# BaseNode.net
KiCad netlist of a schematic drawn in Altium Designer
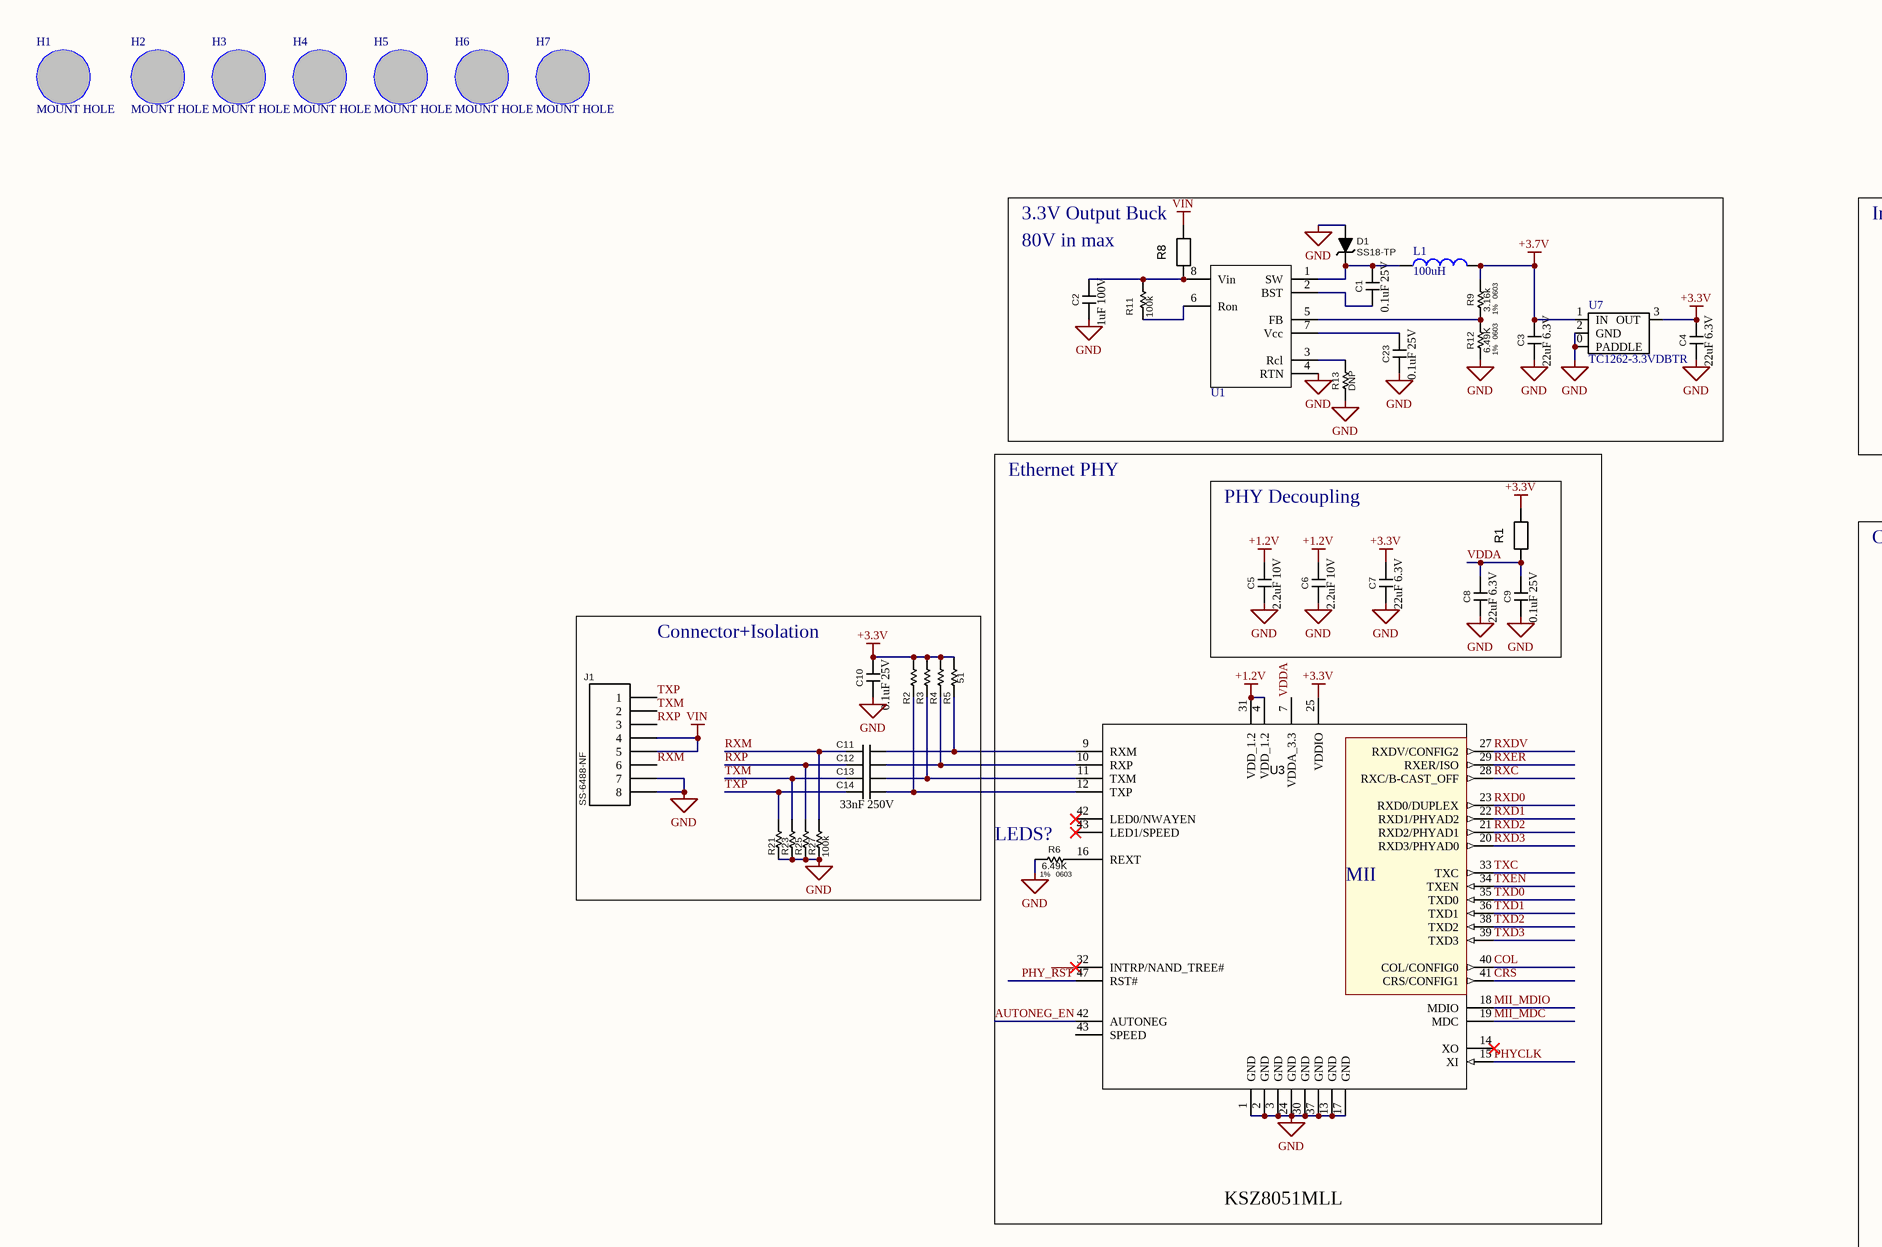
[diagram p0: BaseNode.SchDoc, top left]
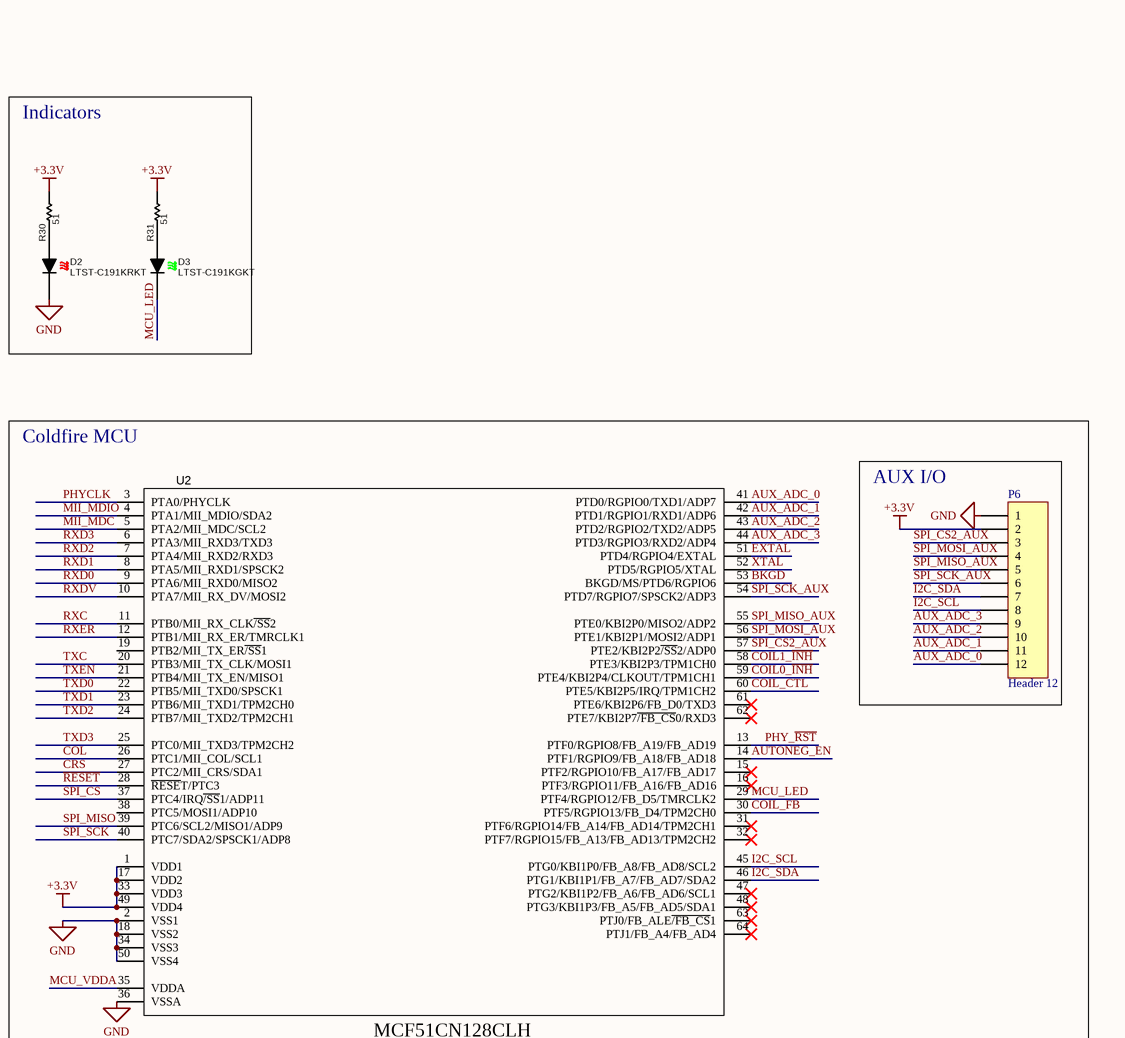
[diagram p1: BaseNode.SchDoc, top right]
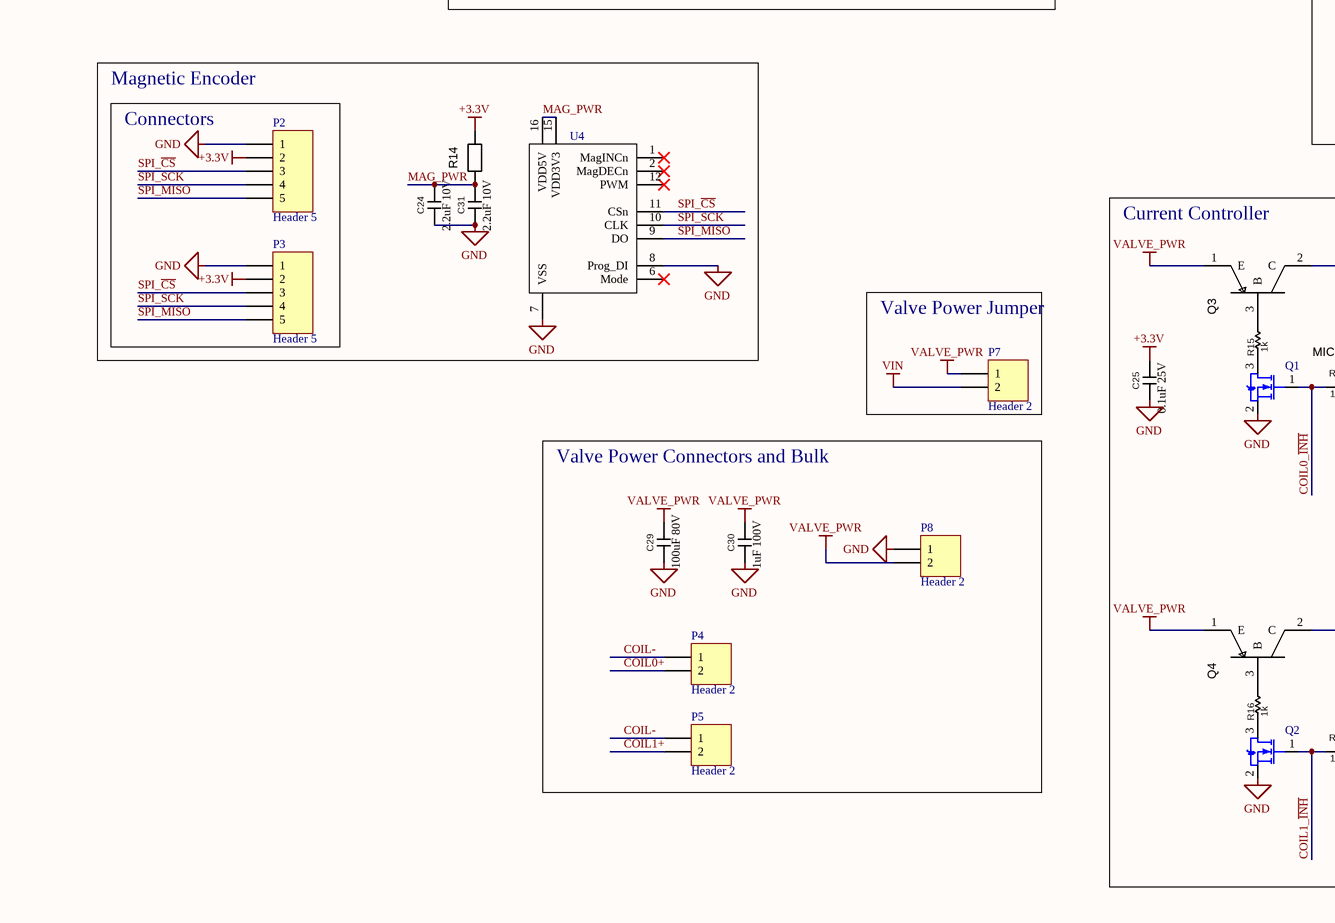
[diagram p2: BaseNode.SchDoc, bottom left]
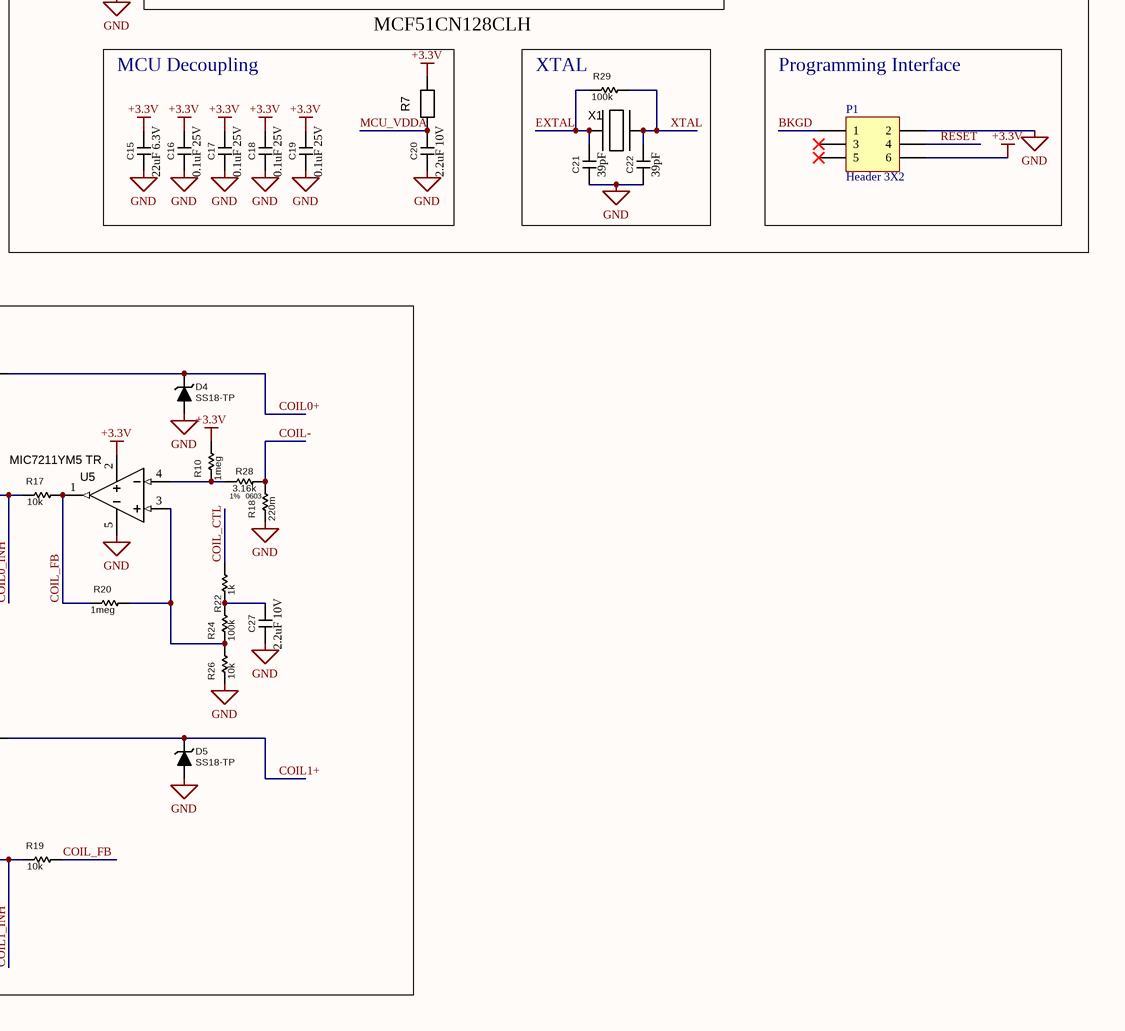
[diagram p3: BaseNode.SchDoc, bottom right]

(export (version "E")
  (design (tool "Eeschema 10.0.6"))
  (components
    (comp (ref "C1")
      (value "0.1uF 25V")
      (footprint "whong:0603")
      (description "Capacitor")
      (fields (field (name "MANUFACTURER") "Murata Electronics North America"))
      (libsource (lib "whong") (part "Capacitor"))
    )
    (comp (ref "C2")
      (value "1uF 100V")
      (footprint "whong:0805")
      (description "Capacitor")
      (fields (field (name "MANUFACTURER") "TDK Corporation"))
      (libsource (lib "whong") (part "Capacitor"))
    )
    (comp (ref "C3")
      (value "22uF 6.3V")
      (footprint "whong:1206")
      (description "Capacitor")
      (fields (field (name "MANUFACTURER") "Taiyo Yuden"))
      (libsource (lib "whong") (part "Capacitor"))
    )
    (comp (ref "C4")
      (value "22uF 6.3V")
      (footprint "whong:1206")
      (description "Capacitor")
      (fields (field (name "MANUFACTURER") "Taiyo Yuden"))
      (libsource (lib "whong") (part "Capacitor"))
    )
    (comp (ref "C5")
      (value "2.2uF 10V")
      (footprint "whong:0603")
      (description "Capacitor")
      (fields (field (name "MANUFACTURER") "Taiyo Yuden"))
      (libsource (lib "whong") (part "Capacitor"))
    )
    (comp (ref "C6")
      (value "2.2uF 10V")
      (footprint "whong:0603")
      (description "Capacitor")
      (fields (field (name "MANUFACTURER") "Taiyo Yuden"))
      (libsource (lib "whong") (part "Capacitor"))
    )
    (comp (ref "C7")
      (value "22uF 6.3V")
      (footprint "whong:1206")
      (description "Capacitor")
      (fields (field (name "MANUFACTURER") "Taiyo Yuden"))
      (libsource (lib "whong") (part "Capacitor"))
    )
    (comp (ref "C8")
      (value "22uF 6.3V")
      (footprint "whong:1206")
      (description "Capacitor")
      (fields (field (name "MANUFACTURER") "Taiyo Yuden"))
      (libsource (lib "whong") (part "Capacitor"))
    )
    (comp (ref "C9")
      (value "0.1uF 25V")
      (footprint "whong:0603")
      (description "Capacitor")
      (fields (field (name "MANUFACTURER") "Murata Electronics North America"))
      (libsource (lib "whong") (part "Capacitor"))
    )
    (comp (ref "C10")
      (value "0.1uF 25V")
      (footprint "whong:0603")
      (description "Capacitor")
      (fields (field (name "MANUFACTURER") "Murata Electronics North America"))
      (libsource (lib "whong") (part "Capacitor"))
    )
    (comp (ref "C11")
      (value "33nF 250V")
      (footprint "whong:0805")
      (description "Capacitor")
      (fields (field (name "MANUFACTURER") "TDK Corporation"))
      (libsource (lib "whong") (part "Capacitor"))
    )
    (comp (ref "C12")
      (value "33nF 250V")
      (footprint "whong:0805")
      (description "Capacitor")
      (fields (field (name "MANUFACTURER") "TDK Corporation"))
      (libsource (lib "whong") (part "Capacitor"))
    )
    (comp (ref "C13")
      (value "33nF 250V")
      (footprint "whong:0805")
      (description "Capacitor")
      (fields (field (name "MANUFACTURER") "TDK Corporation"))
      (libsource (lib "whong") (part "Capacitor"))
    )
    (comp (ref "C14")
      (value "33nF 250V")
      (footprint "whong:0805")
      (description "Capacitor")
      (fields (field (name "MANUFACTURER") "TDK Corporation"))
      (libsource (lib "whong") (part "Capacitor"))
    )
    (comp (ref "C15")
      (value "22uF 6.3V")
      (footprint "whong:1206")
      (description "Capacitor")
      (fields (field (name "MANUFACTURER") "Taiyo Yuden"))
      (libsource (lib "whong") (part "Capacitor"))
    )
    (comp (ref "C16")
      (value "0.1uF 25V")
      (footprint "whong:0603")
      (description "Capacitor")
      (fields (field (name "MANUFACTURER") "Murata Electronics North America"))
      (libsource (lib "whong") (part "Capacitor"))
    )
    (comp (ref "C17")
      (value "0.1uF 25V")
      (footprint "whong:0603")
      (description "Capacitor")
      (fields (field (name "MANUFACTURER") "Murata Electronics North America"))
      (libsource (lib "whong") (part "Capacitor"))
    )
    (comp (ref "C18")
      (value "0.1uF 25V")
      (footprint "whong:0603")
      (description "Capacitor")
      (fields (field (name "MANUFACTURER") "Murata Electronics North America"))
      (libsource (lib "whong") (part "Capacitor"))
    )
    (comp (ref "C19")
      (value "0.1uF 25V")
      (footprint "whong:0603")
      (description "Capacitor")
      (fields (field (name "MANUFACTURER") "Murata Electronics North America"))
      (libsource (lib "whong") (part "Capacitor"))
    )
    (comp (ref "C20")
      (value "2.2uF 10V")
      (footprint "whong:0603")
      (description "Capacitor")
      (fields (field (name "MANUFACTURER") "Taiyo Yuden"))
      (libsource (lib "whong") (part "Capacitor"))
    )
    (comp (ref "C21")
      (value "39pF")
      (footprint "whong:0603")
      (description "Capacitor")
      (fields (field (name "MANUFACTURER") "TDK Corporation"))
      (libsource (lib "whong") (part "Capacitor"))
    )
    (comp (ref "C22")
      (value "39pF")
      (footprint "whong:0603")
      (description "Capacitor")
      (fields (field (name "MANUFACTURER") "TDK Corporation"))
      (libsource (lib "whong") (part "Capacitor"))
    )
    (comp (ref "C23")
      (value "0.1uF 25V")
      (footprint "whong:0603")
      (description "Capacitor")
      (fields (field (name "MANUFACTURER") "Murata Electronics North America"))
      (libsource (lib "whong") (part "Capacitor"))
    )
    (comp (ref "C24")
      (value "2.2uF 10V")
      (footprint "whong:0603")
      (description "Capacitor")
      (fields (field (name "MANUFACTURER") "Taiyo Yuden"))
      (libsource (lib "whong") (part "Capacitor"))
    )
    (comp (ref "C25")
      (value "0.1uF 25V")
      (footprint "whong:0603")
      (description "Capacitor")
      (fields (field (name "MANUFACTURER") "Murata Electronics North America"))
      (libsource (lib "whong") (part "Capacitor"))
    )
    (comp (ref "C27")
      (value "2.2uF 10V")
      (footprint "whong:0603")
      (description "Capacitor")
      (fields (field (name "MANUFACTURER") "Taiyo Yuden"))
      (libsource (lib "whong") (part "Capacitor"))
    )
    (comp (ref "C29")
      (value "100uF 80V")
      (footprint "whong:Capacitor 12mm DIA POLAR")
      (description "Capacitor")
      (fields (field (name "MANUFACTURER") "Panasonic Electronic Components"))
      (libsource (lib "whong") (part "Capacitor"))
    )
    (comp (ref "C30")
      (value "1uF 100V")
      (footprint "whong:0805")
      (description "Capacitor")
      (fields (field (name "MANUFACTURER") "TDK Corporation"))
      (libsource (lib "whong") (part "Capacitor"))
    )
    (comp (ref "C31")
      (value "2.2uF 10V")
      (footprint "whong:0603")
      (description "Capacitor")
      (fields (field (name "MANUFACTURER") "Taiyo Yuden"))
      (libsource (lib "whong") (part "Capacitor"))
    )
    (comp (ref "D1")
      (value "CDBA140-G")
      (footprint "SMA-DIODE")
      (description "DIODE SCHOTTKY 40V 1A SMA")
      (fields (field (name "MANUFACTURER") "Micro Commercial Co") (field (name "MANUFACTURERPN") "SS18-TP"))
      (libsource (lib "whong") (part "CDBA140-G"))
    )
    (comp (ref "D2")
      (value "WP113IDT")
      (footprint "whong:0603 - LED")
      (description "LED RECT 2X5MM 625NM RED DIFF")
      (fields (field (name "MANUFACTURER") "Lite-On Inc") (field (name "MANUFACTURERPN") "LTST-C191KRKT"))
      (libsource (lib "whong") (part "WP113IDT"))
    )
    (comp (ref "D3")
      (value "WP113GDT")
      (footprint "whong:0603 - LED")
      (description "LED RECT 2X5MM 568NM GRN DIFF")
      (fields (field (name "MANUFACTURER") "Lite-On Inc") (field (name "MANUFACTURERPN") "LTST-C191KGKT"))
      (libsource (lib "whong") (part "WP113GDT"))
    )
    (comp (ref "D4")
      (value "CDBA140-G")
      (footprint "SMA-DIODE")
      (description "DIODE SCHOTTKY 40V 1A SMA")
      (fields (field (name "MANUFACTURER") "Micro Commercial Co") (field (name "MANUFACTURERPN") "SS18-TP"))
      (libsource (lib "whong") (part "CDBA140-G"))
    )
    (comp (ref "D5")
      (value "CDBA140-G")
      (footprint "SMA-DIODE")
      (description "DIODE SCHOTTKY 40V 1A SMA")
      (fields (field (name "MANUFACTURER") "Micro Commercial Co") (field (name "MANUFACTURERPN") "SS18-TP"))
      (libsource (lib "whong") (part "CDBA140-G"))
    )
    (comp (ref "H1")
      (value "MOUNT HOLE")
      (footprint "MOUNT_HOLE")
      (libsource (lib "whong") (part "MOUNT HOLE"))
    )
    (comp (ref "H2")
      (value "MOUNT HOLE")
      (footprint "MOUNT_HOLE")
      (libsource (lib "whong") (part "MOUNT HOLE"))
    )
    (comp (ref "H3")
      (value "MOUNT HOLE")
      (footprint "MOUNT_HOLE")
      (libsource (lib "whong") (part "MOUNT HOLE"))
    )
    (comp (ref "H4")
      (value "MOUNT HOLE")
      (footprint "MOUNT_HOLE")
      (libsource (lib "whong") (part "MOUNT HOLE"))
    )
    (comp (ref "H5")
      (value "MOUNT HOLE")
      (footprint "MOUNT_HOLE")
      (libsource (lib "whong") (part "MOUNT HOLE"))
    )
    (comp (ref "H6")
      (value "MOUNT HOLE")
      (footprint "MOUNT_HOLE")
      (libsource (lib "whong") (part "MOUNT HOLE"))
    )
    (comp (ref "H7")
      (value "MOUNT HOLE")
      (footprint "MOUNT_HOLE")
      (libsource (lib "whong") (part "MOUNT HOLE"))
    )
    (comp (ref "J1")
      (value "SS-6488-NF")
      (footprint "whong:SS-6488-NF")
      (description "CONN 8-8 MOD JACK")
      (fields (field (name "MANUFACTURER") "Stewart Connector"))
      (libsource (lib "whong") (part "SS-6488-NF"))
    )
    (comp (ref "L1")
      (value "100uH")
      (footprint "whong:NR6028 Inductor")
      (description "Inductor")
      (fields (field (name "MANUFACTURER") "Taiyo Yuden"))
      (libsource (lib "Miscellaneous Devices") (part "Inductor"))
    )
    (comp (ref "P1")
      (value "Header 3X2")
      (footprint "HDR2X3")
      (description "Header, 3-Pin, Dual row")
      (fields (field (name "PUBLISHER") "Altium Limited"))
      (libsource (lib "Miscellaneous Connectors") (part "Header 3X2"))
    )
    (comp (ref "P2")
      (value "Header 5")
      (footprint "HDR1X5")
      (description "Header, 5-Pin")
      (fields (field (name "PUBLISHER") "Altium Limited"))
      (libsource (lib "Miscellaneous Connectors") (part "Header 5"))
    )
    (comp (ref "P3")
      (value "Header 5")
      (footprint "HDR1X5")
      (description "Header, 5-Pin")
      (fields (field (name "PUBLISHER") "Altium Limited"))
      (libsource (lib "Miscellaneous Connectors") (part "Header 5"))
    )
    (comp (ref "P4")
      (value "Header 2")
      (footprint "HDR1X2")
      (description "Header, 2-Pin")
      (fields (field (name "PUBLISHER") "Altium Limited"))
      (libsource (lib "Miscellaneous Connectors") (part "Header 2"))
    )
    (comp (ref "P5")
      (value "Header 2")
      (footprint "HDR1X2")
      (description "Header, 2-Pin")
      (fields (field (name "PUBLISHER") "Altium Limited"))
      (libsource (lib "Miscellaneous Connectors") (part "Header 2"))
    )
    (comp (ref "P6")
      (value "Header 12")
      (footprint "HDR1X12")
      (description "Header, 12-Pin")
      (fields (field (name "PUBLISHER") "Altium Limited"))
      (libsource (lib "Miscellaneous Connectors") (part "Header 12"))
    )
    (comp (ref "P7")
      (value "Header 2")
      (footprint "HDR1X2")
      (description "Header, 2-Pin")
      (fields (field (name "PUBLISHER") "Altium Limited"))
      (libsource (lib "Miscellaneous Connectors") (part "Header 2"))
    )
    (comp (ref "P8")
      (value "Header 2")
      (footprint "HDR1X2")
      (description "Header, 2-Pin")
      (fields (field (name "PUBLISHER") "Altium Limited"))
      (libsource (lib "Miscellaneous Connectors") (part "Header 2"))
    )
    (comp (ref "Q1")
      (value "NFET")
      (footprint "whong:SOT-23")
      (description "FET N-CH 100V 170MA SOT-23")
      (fields (field (name "MANUFACTURER") "Fairchild Semiconductor"))
      (libsource (lib "whong") (part "BSS123"))
    )
    (comp (ref "Q2")
      (value "NFET")
      (footprint "whong:SOT-23")
      (description "FET N-CH 100V 170MA SOT-23")
      (fields (field (name "MANUFACTURER") "Fairchild Semiconductor"))
      (libsource (lib "whong") (part "BSS123"))
    )
    (comp (ref "Q3")
      (value "~")
      (footprint "whong:SOT-89 - PBSS305PX")
      (description "TRANS PNP 80V 4A SOT89")
      (fields (field (name "MANUFACTURER") "NXP Semiconductors"))
      (libsource (lib "whong") (part "PBSS305PX,115"))
    )
    (comp (ref "Q4")
      (value "~")
      (footprint "whong:SOT-89 - PBSS305PX")
      (description "TRANS PNP 80V 4A SOT89")
      (fields (field (name "MANUFACTURER") "NXP Semiconductors"))
      (libsource (lib "whong") (part "PBSS305PX,115"))
    )
    (comp (ref "R1")
      (value "LM4041EIM3X-1.2_1")
      (footprint "whong:0603")
      (description "Ferrite")
      (fields (field (name "MANUFACTURER") "TDK Corporation"))
      (libsource (lib "whong") (part "LM4041EIM3X-1.2_1"))
    )
    (comp (ref "R2")
      (value "51")
      (footprint "whong:0603")
      (description "Resistor")
      (fields (field (name "MANUFACTURER") "Yageo") (field (name "TOLERANCE") "5%"))
      (libsource (lib "whong") (part "Resistor"))
    )
    (comp (ref "R3")
      (value "51")
      (footprint "whong:0603")
      (description "Resistor")
      (fields (field (name "MANUFACTURER") "Yageo") (field (name "TOLERANCE") "5%"))
      (libsource (lib "whong") (part "Resistor"))
    )
    (comp (ref "R4")
      (value "51")
      (footprint "whong:0603")
      (description "Resistor")
      (fields (field (name "MANUFACTURER") "Yageo") (field (name "TOLERANCE") "5%"))
      (libsource (lib "whong") (part "Resistor"))
    )
    (comp (ref "R5")
      (value "51")
      (footprint "whong:0603")
      (description "Resistor")
      (fields (field (name "MANUFACTURER") "Yageo") (field (name "TOLERANCE") "5%"))
      (libsource (lib "whong") (part "Resistor"))
    )
    (comp (ref "R6")
      (value "6.49K")
      (footprint "whong:0603")
      (description "Resistor")
      (fields
        (field (name "MANUFACTURER") "Yageo")
        (field (name "PACKAGE") "0603")
        (field (name "TOLERANCE") "1%")
      )
      (libsource (lib "JamesWhong") (part "Resistor"))
    )
    (comp (ref "R7")
      (value "LM4041EIM3X-1.2_1")
      (footprint "whong:0603")
      (description "Ferrite")
      (fields (field (name "MANUFACTURER") "TDK Corporation"))
      (libsource (lib "whong") (part "LM4041EIM3X-1.2_1"))
    )
    (comp (ref "R8")
      (value "LM4041EIM3X-1.2_1")
      (footprint "whong:0603")
      (description "Ferrite")
      (fields (field (name "MANUFACTURER") "TDK Corporation"))
      (libsource (lib "whong") (part "LM4041EIM3X-1.2_1"))
    )
    (comp (ref "R9")
      (value "3.16k")
      (footprint "whong:0603")
      (description "Resistor")
      (fields
        (field (name "MANUFACTURER") "Yageo")
        (field (name "PACKAGE") "0603")
        (field (name "TOLERANCE") "1%")
      )
      (libsource (lib "JamesWhong") (part "Resistor"))
    )
    (comp (ref "R10")
      (value "1meg")
      (footprint "whong:0603")
      (description "Resistor")
      (fields (field (name "MANUFACTURER") "Yageo") (field (name "TOLERANCE") "5%"))
      (libsource (lib "whong") (part "Resistor"))
    )
    (comp (ref "R11")
      (value "100k")
      (footprint "whong:0603")
      (description "Resistor")
      (fields (field (name "MANUFACTURER") "Yageo"))
      (libsource (lib "whong") (part "Resistor"))
    )
    (comp (ref "R12")
      (value "6.49K")
      (footprint "whong:0603")
      (description "Resistor")
      (fields
        (field (name "MANUFACTURER") "Yageo")
        (field (name "PACKAGE") "0603")
        (field (name "TOLERANCE") "1%")
      )
      (libsource (lib "JamesWhong") (part "Resistor"))
    )
    (comp (ref "R13")
      (value "DNP")
      (footprint "whong:0603")
      (description "Resistor")
      (fields (field (name "TOLERANCE") "1%"))
      (libsource (lib "JamesWhong") (part "Resistor"))
    )
    (comp (ref "R14")
      (value "LM4041EIM3X-1.2_1")
      (footprint "whong:0603")
      (description "Ferrite")
      (fields (field (name "MANUFACTURER") "TDK Corporation"))
      (libsource (lib "whong") (part "LM4041EIM3X-1.2_1"))
    )
    (comp (ref "R15")
      (value "1k")
      (footprint "whong:0603")
      (description "Resistor")
      (fields (field (name "MANUFACTURER") "Yageo") (field (name "TOLERANCE") "5%"))
      (libsource (lib "whong") (part "Resistor"))
    )
    (comp (ref "R16")
      (value "1k")
      (footprint "whong:0603")
      (description "Resistor")
      (fields (field (name "MANUFACTURER") "Yageo") (field (name "TOLERANCE") "5%"))
      (libsource (lib "whong") (part "Resistor"))
    )
    (comp (ref "R17")
      (value "10k")
      (footprint "whong:0603")
      (description "Resistor")
      (fields (field (name "MANUFACTURER") "Yageo"))
      (libsource (lib "whong") (part "Resistor"))
    )
    (comp (ref "R18")
      (value "220m")
      (footprint "whong:0805")
      (description "Resistor")
      (fields (field (name "MANUFACTURER") "Susumu"))
      (libsource (lib "whong") (part "Resistor"))
    )
    (comp (ref "R19")
      (value "10k")
      (footprint "whong:0603")
      (description "Resistor")
      (fields (field (name "MANUFACTURER") "Yageo"))
      (libsource (lib "whong") (part "Resistor"))
    )
    (comp (ref "R20")
      (value "1meg")
      (footprint "whong:0603")
      (description "Resistor")
      (fields (field (name "MANUFACTURER") "Yageo") (field (name "TOLERANCE") "5%"))
      (libsource (lib "whong") (part "Resistor"))
    )
    (comp (ref "R21")
      (value "100k")
      (footprint "whong:0603")
      (description "Resistor")
      (fields (field (name "MANUFACTURER") "Yageo"))
      (libsource (lib "whong") (part "Resistor"))
    )
    (comp (ref "R22")
      (value "1k")
      (footprint "whong:0603")
      (description "Resistor")
      (fields (field (name "MANUFACTURER") "Yageo") (field (name "TOLERANCE") "5%"))
      (libsource (lib "whong") (part "Resistor"))
    )
    (comp (ref "R23")
      (value "100k")
      (footprint "whong:0603")
      (description "Resistor")
      (fields (field (name "MANUFACTURER") "Yageo"))
      (libsource (lib "whong") (part "Resistor"))
    )
    (comp (ref "R24")
      (value "100k")
      (footprint "whong:0603")
      (description "Resistor")
      (fields (field (name "MANUFACTURER") "Yageo"))
      (libsource (lib "whong") (part "Resistor"))
    )
    (comp (ref "R25")
      (value "100k")
      (footprint "whong:0603")
      (description "Resistor")
      (fields (field (name "MANUFACTURER") "Yageo"))
      (libsource (lib "whong") (part "Resistor"))
    )
    (comp (ref "R26")
      (value "10k")
      (footprint "whong:0603")
      (description "Resistor")
      (fields (field (name "MANUFACTURER") "Yageo"))
      (libsource (lib "whong") (part "Resistor"))
    )
    (comp (ref "R27")
      (value "100k")
      (footprint "whong:0603")
      (description "Resistor")
      (fields (field (name "MANUFACTURER") "Yageo"))
      (libsource (lib "whong") (part "Resistor"))
    )
    (comp (ref "R28")
      (value "3.16k")
      (footprint "whong:0603")
      (description "Resistor")
      (fields
        (field (name "MANUFACTURER") "Yageo")
        (field (name "PACKAGE") "0603")
        (field (name "TOLERANCE") "1%")
      )
      (libsource (lib "JamesWhong") (part "Resistor"))
    )
    (comp (ref "R29")
      (value "100k")
      (footprint "whong:0603")
      (description "Resistor")
      (fields (field (name "MANUFACTURER") "Yageo"))
      (libsource (lib "whong") (part "Resistor"))
    )
    (comp (ref "R30")
      (value "51")
      (footprint "whong:0603")
      (description "Resistor")
      (fields (field (name "MANUFACTURER") "Yageo") (field (name "TOLERANCE") "5%"))
      (libsource (lib "whong") (part "Resistor"))
    )
    (comp (ref "R31")
      (value "51")
      (footprint "whong:0603")
      (description "Resistor")
      (fields (field (name "MANUFACTURER") "Yageo") (field (name "TOLERANCE") "5%"))
      (libsource (lib "whong") (part "Resistor"))
    )
    (comp (ref "U1")
      (value "LM5007MM/NOPB")
      (footprint "whong:MSOP-8")
      (description "BUCK ADJ .5A 8MSOP")
      (fields (field (name "MANUFACTURER") "National Semiconductor"))
      (libsource (lib "whong") (part "LM5007MM/NOPB"))
    )
    (comp (ref "U2")
      (value "MCF51CN128CLH")
      (footprint "LQFP-64 10x10mm .5mm pitch")
      (description "MCU Coldfire w/ Ethernet")
      (fields (field (name "MANUFACTURER") "Freescale Semiconductor"))
      (libsource (lib "whong") (part "MCF51CN128CLH"))
    )
    (comp (ref "U3")
      (value "KSZ8051MLL")
      (footprint "LQFP-48 7x7mm 0.5mm pitch")
      (description "Ethernet PHY MII")
      (fields (field (name "MANUFACTURER") "Micrel Inc"))
      (libsource (lib "whong") (part "KSZ8051MLL"))
    )
    (comp (ref "U4")
      (value "AS5045-ASSU")
      (footprint "whong:SSOP-16")
      (description "IC ENCODER PROG 12-BIT 16-SSOP")
      (fields (field (name "MANUFACTURER") "AMS"))
      (libsource (lib "whong") (part "AS5045-ASSU"))
    )
    (comp (ref "U5")
      (value "MIC7211YM5 TR")
      (footprint "whong:SOT-23-5")
      (description "IC COMPARATOR R-R SOT-23-5")
      (fields (field (name "MANUFACTURER") "Micrel Inc"))
      (libsource (lib "whong") (part "MIC7221YM5 TR"))
    )
    (comp (ref "U7")
      (value "TC1262-3.3VDBTR")
      (footprint "bdilib:SOT-223")
      (description "Regulator IC CMOS LDO 3.3V 500MA SOT223-3")
      (fields
        (field (name "MANUFACTURER") "Microchip Technology")
        (field (name "MANUFACTURERPN") "TC1262-3.3VDBTR")
      )
      (libsource (lib "whong") (part "TC1262-3.3VDBTR"))
    )
    (comp (ref "X1")
      (value "ECS-250-20-3X-EN-TR")
      (footprint "CSM-3X")
      (description "CRYSTAL 25.00000 MHZ 20PF SMD")
      (fields (field (name "MANUFACTURER") "ECS Inc"))
      (libsource (lib "whong") (part "ECS-250-20-3X-EN-TR"))
    )
  )
  (nets
    (net (code "1") (name "+1.2V") (class "Default")
      (node (ref "C5") (pin "2") (pinfunction "2_2") (pintype "passive"))
      (node (ref "C6") (pin "2") (pinfunction "2_2") (pintype "passive"))
      (node (ref "U3") (pin "31") (pinfunction "VDD_1.2_31") (pintype "passive"))
      (node (ref "U3") (pin "4") (pinfunction "VDD_1.2_4") (pintype "passive"))
    )
    (net (code "2") (name "+3.3V") (class "Default")
      (node (ref "C10") (pin "2") (pinfunction "2_2") (pintype "passive"))
      (node (ref "C15") (pin "2") (pinfunction "2_2") (pintype "passive"))
      (node (ref "C16") (pin "2") (pinfunction "2_2") (pintype "passive"))
      (node (ref "C17") (pin "2") (pinfunction "2_2") (pintype "passive"))
      (node (ref "C18") (pin "2") (pinfunction "2_2") (pintype "passive"))
      (node (ref "C19") (pin "2") (pinfunction "2_2") (pintype "passive"))
      (node (ref "C25") (pin "2") (pinfunction "2_2") (pintype "passive"))
      (node (ref "C4") (pin "2") (pinfunction "2_2") (pintype "passive"))
      (node (ref "C7") (pin "2") (pinfunction "2_2") (pintype "passive"))
      (node (ref "P1") (pin "6") (pinfunction "6_6") (pintype "passive"))
      (node (ref "P2") (pin "2") (pinfunction "2_2") (pintype "passive"))
      (node (ref "P3") (pin "2") (pinfunction "2_2") (pintype "passive"))
      (node (ref "P6") (pin "2") (pinfunction "2_2") (pintype "passive"))
      (node (ref "R1") (pin "1") (pinfunction "K_1") (pintype "passive"))
      (node (ref "R10") (pin "2") (pinfunction "2_2") (pintype "passive"))
      (node (ref "R14") (pin "1") (pinfunction "K_1") (pintype "passive"))
      (node (ref "R2") (pin "2") (pinfunction "2_2") (pintype "passive"))
      (node (ref "R3") (pin "2") (pinfunction "2_2") (pintype "passive"))
      (node (ref "R30") (pin "2") (pinfunction "2_2") (pintype "passive"))
      (node (ref "R31") (pin "2") (pinfunction "2_2") (pintype "passive"))
      (node (ref "R4") (pin "2") (pinfunction "2_2") (pintype "passive"))
      (node (ref "R5") (pin "2") (pinfunction "2_2") (pintype "passive"))
      (node (ref "R7") (pin "1") (pinfunction "K_1") (pintype "passive"))
      (node (ref "U2") (pin "1") (pinfunction "VDD1_1") (pintype "passive"))
      (node (ref "U2") (pin "17") (pinfunction "VDD2_17") (pintype "passive"))
      (node (ref "U2") (pin "33") (pinfunction "VDD3_33") (pintype "passive"))
      (node (ref "U2") (pin "49") (pinfunction "VDD4_49") (pintype "passive"))
      (node (ref "U3") (pin "25") (pinfunction "VDDIO_25") (pintype "passive"))
      (node (ref "U5") (pin "2") (pinfunction "V+_2") (pintype "power_in"))
      (node (ref "U7") (pin "3") (pinfunction "OUT_3") (pintype "passive"))
    )
    (net (code "3") (name "+3.7V") (class "Default")
      (node (ref "C3") (pin "2") (pinfunction "2_2") (pintype "passive"))
      (node (ref "L1") (pin "2") (pinfunction "2_2") (pintype "passive"))
      (node (ref "R9") (pin "2") (pinfunction "2_2") (pintype "passive"))
      (node (ref "U7") (pin "1") (pinfunction "IN_1") (pintype "passive"))
    )
    (net (code "4") (name "/AUTONEG_EN") (class "Default")
      (node (ref "U2") (pin "14") (pinfunction "PTF1/RGPIO9/FB_A18/FB_AD18_14") (pintype "passive"))
      (node (ref "U3") (pin "42") (pinfunction "AUTONEG_42") (pintype "passive"))
    )
    (net (code "5") (name "/AUX_ADC_0") (class "Default")
      (node (ref "P6") (pin "12") (pinfunction "12_12") (pintype "passive"))
      (node (ref "U2") (pin "41") (pinfunction "PTD0/RGPIO0/TXD1/ADP7_41") (pintype "passive"))
    )
    (net (code "6") (name "/AUX_ADC_1") (class "Default")
      (node (ref "P6") (pin "11") (pinfunction "11_11") (pintype "passive"))
      (node (ref "U2") (pin "42") (pinfunction "PTD1/RGPIO1/RXD1/ADP6_42") (pintype "passive"))
    )
    (net (code "7") (name "/AUX_ADC_2") (class "Default")
      (node (ref "P6") (pin "10") (pinfunction "10_10") (pintype "passive"))
      (node (ref "U2") (pin "43") (pinfunction "PTD2/RGPIO2/TXD2/ADP5_43") (pintype "passive"))
    )
    (net (code "8") (name "/AUX_ADC_3") (class "Default")
      (node (ref "P6") (pin "9") (pinfunction "9_9") (pintype "passive"))
      (node (ref "U2") (pin "44") (pinfunction "PTD3/RGPIO3/RXD2/ADP4_44") (pintype "passive"))
    )
    (net (code "9") (name "/BKGD") (class "Default")
      (node (ref "P1") (pin "1") (pinfunction "1_1") (pintype "passive"))
      (node (ref "U2") (pin "53") (pinfunction "BKGD/MS/PTD6/RGPIO6_53") (pintype "passive"))
    )
    (net (code "10") (name "/COIL-") (class "Default")
      (node (ref "P4") (pin "1") (pinfunction "1_1") (pintype "passive"))
      (node (ref "P5") (pin "1") (pinfunction "1_1") (pintype "passive"))
      (node (ref "R18") (pin "2") (pinfunction "2_2") (pintype "passive"))
      (node (ref "R28") (pin "2") (pinfunction "2_2") (pintype "passive"))
    )
    (net (code "11") (name "/COIL0+") (class "Default")
      (node (ref "D4") (pin "K") (pinfunction "K_K") (pintype "passive"))
      (node (ref "P4") (pin "2") (pinfunction "2_2") (pintype "passive"))
      (node (ref "Q3") (pin "2") (pinfunction "C_2") (pintype "passive"))
    )
    (net (code "12") (name "/COIL0_~{INH}") (class "Default")
      (node (ref "Q1") (pin "1") (pinfunction "G_1") (pintype "passive"))
      (node (ref "R17") (pin "1") (pinfunction "1_1") (pintype "passive"))
      (node (ref "U2") (pin "59") (pinfunction "PTE4/KBI2P4/CLKOUT/TPM1CH1_59") (pintype "passive"))
    )
    (net (code "13") (name "/COIL1+") (class "Default")
      (node (ref "D5") (pin "K") (pinfunction "K_K") (pintype "passive"))
      (node (ref "P5") (pin "2") (pinfunction "2_2") (pintype "passive"))
      (node (ref "Q4") (pin "2") (pinfunction "C_2") (pintype "passive"))
    )
    (net (code "14") (name "/COIL1_~{INH}") (class "Default")
      (node (ref "Q2") (pin "1") (pinfunction "G_1") (pintype "passive"))
      (node (ref "R19") (pin "1") (pinfunction "1_1") (pintype "passive"))
      (node (ref "U2") (pin "58") (pinfunction "PTE3/KBI2P3/TPM1CH0_58") (pintype "passive"))
    )
    (net (code "15") (name "/COIL_CTL") (class "Default")
      (node (ref "R22") (pin "2") (pinfunction "2_2") (pintype "passive"))
      (node (ref "U2") (pin "60") (pinfunction "PTE5/KBI2P5/IRQ/TPM1CH2_60") (pintype "passive"))
    )
    (net (code "16") (name "/COIL_FB") (class "Default")
      (node (ref "R17") (pin "2") (pinfunction "2_2") (pintype "passive"))
      (node (ref "R19") (pin "2") (pinfunction "2_2") (pintype "passive"))
      (node (ref "R20") (pin "1") (pinfunction "1_1") (pintype "passive"))
      (node (ref "U2") (pin "30") (pinfunction "PTF5/RGPIO13/FB_D4/TPM2CH0_30") (pintype "passive"))
      (node (ref "U5") (pin "1") (pinfunction "Out_A_1") (pintype "output"))
    )
    (net (code "17") (name "/COL") (class "Default")
      (node (ref "U2") (pin "26") (pinfunction "PTC1/MII_COL/SCL1_26") (pintype "passive"))
      (node (ref "U3") (pin "40") (pinfunction "COL/CONFIG0_40") (pintype "output"))
    )
    (net (code "18") (name "/CRS") (class "Default")
      (node (ref "U2") (pin "27") (pinfunction "PTC2/MII_CRS/SDA1_27") (pintype "passive"))
      (node (ref "U3") (pin "41") (pinfunction "CRS/CONFIG1_41") (pintype "output"))
    )
    (net (code "19") (name "/EXTAL") (class "Default")
      (node (ref "C21") (pin "2") (pinfunction "2_2") (pintype "passive"))
      (node (ref "R29") (pin "1") (pinfunction "1_1") (pintype "passive"))
      (node (ref "U2") (pin "51") (pinfunction "PTD4/RGPIO4/EXTAL_51") (pintype "passive"))
      (node (ref "X1") (pin "2") (pinfunction "A_2") (pintype "passive"))
    )
    (net (code "20") (name "/I2C_SCL") (class "Default")
      (node (ref "P6") (pin "8") (pinfunction "8_8") (pintype "passive"))
      (node (ref "U2") (pin "45") (pinfunction "PTG0/KBI1P0/FB_A8/FB_AD8/SCL2_45") (pintype "passive"))
    )
    (net (code "21") (name "/I2C_SDA") (class "Default")
      (node (ref "P6") (pin "7") (pinfunction "7_7") (pintype "passive"))
      (node (ref "U2") (pin "46") (pinfunction "PTG1/KBI1P1/FB_A7/FB_AD7/SDA2_46") (pintype "passive"))
    )
    (net (code "22") (name "/MAG_PWR") (class "Default")
      (node (ref "C24") (pin "2") (pinfunction "2_2") (pintype "passive"))
      (node (ref "C31") (pin "2") (pinfunction "2_2") (pintype "passive"))
      (node (ref "R14") (pin "2") (pinfunction "A_2") (pintype "passive"))
      (node (ref "U4") (pin "15") (pinfunction "VDD3V3_15") (pintype "passive"))
      (node (ref "U4") (pin "16") (pinfunction "VDD5V_16") (pintype "passive"))
    )
    (net (code "23") (name "/MCU_LED") (class "Default")
      (node (ref "D3") (pin "K") (pinfunction "K_K") (pintype "passive"))
      (node (ref "U2") (pin "29") (pinfunction "PTF4/RGPIO12/FB_D5/TMRCLK2_29") (pintype "passive"))
    )
    (net (code "24") (name "/MCU_VDDA") (class "Default")
      (node (ref "C20") (pin "2") (pinfunction "2_2") (pintype "passive"))
      (node (ref "R7") (pin "2") (pinfunction "A_2") (pintype "passive"))
      (node (ref "U2") (pin "35") (pinfunction "VDDA_35") (pintype "passive"))
    )
    (net (code "25") (name "/MII_MDC") (class "Default")
      (node (ref "U2") (pin "5") (pinfunction "PTA2/MII_MDC/SCL2_5") (pintype "passive"))
      (node (ref "U3") (pin "19") (pinfunction "MDC_19") (pintype "passive"))
    )
    (net (code "26") (name "/MII_MDIO") (class "Default")
      (node (ref "U2") (pin "4") (pinfunction "PTA1/MII_MDIO/SDA2_4") (pintype "passive"))
      (node (ref "U3") (pin "18") (pinfunction "MDIO_18") (pintype "passive"))
    )
    (net (code "27") (name "/PHYCLK") (class "Default")
      (node (ref "U2") (pin "3") (pinfunction "PTA0/PHYCLK_3") (pintype "passive"))
      (node (ref "U3") (pin "15") (pinfunction "XI_15") (pintype "input"))
    )
    (net (code "28") (name "/PHY_~{RST}") (class "Default")
      (node (ref "U2") (pin "13") (pinfunction "PTF0/RGPIO8/FB_A19/FB_AD19_13") (pintype "passive"))
      (node (ref "U3") (pin "47") (pinfunction "RST#_47") (pintype "passive"))
    )
    (net (code "29") (name "/RXC") (class "Default")
      (node (ref "U2") (pin "11") (pinfunction "PTB0/MII_RX_CLK~{/SS}2_11") (pintype "passive"))
      (node (ref "U3") (pin "28") (pinfunction "RXC/B-CAST_OFF_28") (pintype "output"))
    )
    (net (code "30") (name "/RXD0") (class "Default")
      (node (ref "U2") (pin "9") (pinfunction "PTA6/MII_RXD0/MISO2_9") (pintype "passive"))
      (node (ref "U3") (pin "23") (pinfunction "RXD0/DUPLEX_23") (pintype "output"))
    )
    (net (code "31") (name "/RXD1") (class "Default")
      (node (ref "U2") (pin "8") (pinfunction "PTA5/MII_RXD1/SPSCK2_8") (pintype "passive"))
      (node (ref "U3") (pin "22") (pinfunction "RXD1/PHYAD2_22") (pintype "output"))
    )
    (net (code "32") (name "/RXD2") (class "Default")
      (node (ref "U2") (pin "7") (pinfunction "PTA4/MII_RXD2/RXD3_7") (pintype "passive"))
      (node (ref "U3") (pin "21") (pinfunction "RXD2/PHYAD1_21") (pintype "output"))
    )
    (net (code "33") (name "/RXD3") (class "Default")
      (node (ref "U2") (pin "6") (pinfunction "PTA3/MII_RXD3/TXD3_6") (pintype "passive"))
      (node (ref "U3") (pin "20") (pinfunction "RXD3/PHYAD0_20") (pintype "output"))
    )
    (net (code "34") (name "/RXDV") (class "Default")
      (node (ref "U2") (pin "10") (pinfunction "PTA7/MII_RX_DV/MOSI2_10") (pintype "passive"))
      (node (ref "U3") (pin "27") (pinfunction "RXDV/CONFIG2_27") (pintype "output"))
    )
    (net (code "35") (name "/RXER") (class "Default")
      (node (ref "U2") (pin "12") (pinfunction "PTB1/MII_RX_ER/TMRCLK1_12") (pintype "passive"))
      (node (ref "U3") (pin "29") (pinfunction "RXER/ISO_29") (pintype "output"))
    )
    (net (code "36") (name "/RXM") (class "Default")
      (node (ref "C11") (pin "1") (pinfunction "1_1") (pintype "passive"))
      (node (ref "J1") (pin "6") (pinfunction "6_6") (pintype "passive"))
      (node (ref "R27") (pin "2") (pinfunction "2_2") (pintype "passive"))
    )
    (net (code "37") (name "/RXP") (class "Default")
      (node (ref "C12") (pin "1") (pinfunction "1_1") (pintype "passive"))
      (node (ref "J1") (pin "3") (pinfunction "3_3") (pintype "passive"))
      (node (ref "R25") (pin "2") (pinfunction "2_2") (pintype "passive"))
    )
    (net (code "38") (name "/SPI_MISO") (class "Default")
      (node (ref "P2") (pin "5") (pinfunction "5_5") (pintype "passive"))
      (node (ref "P3") (pin "5") (pinfunction "5_5") (pintype "passive"))
      (node (ref "U2") (pin "39") (pinfunction "PTC6/SCL2/MISO1/ADP9_39") (pintype "passive"))
      (node (ref "U4") (pin "9") (pinfunction "DO_9") (pintype "passive"))
    )
    (net (code "39") (name "/SPI_MISO_AUX") (class "Default")
      (node (ref "P6") (pin "5") (pinfunction "5_5") (pintype "passive"))
      (node (ref "U2") (pin "55") (pinfunction "PTE0/KBI2P0/MISO2/ADP2_55") (pintype "passive"))
    )
    (net (code "40") (name "/SPI_MOSI_AUX") (class "Default")
      (node (ref "P6") (pin "4") (pinfunction "4_4") (pintype "passive"))
      (node (ref "U2") (pin "56") (pinfunction "PTE1/KBI2P1/MOSI2/ADP1_56") (pintype "passive"))
    )
    (net (code "41") (name "/SPI_SCK") (class "Default")
      (node (ref "P2") (pin "4") (pinfunction "4_4") (pintype "passive"))
      (node (ref "P3") (pin "4") (pinfunction "4_4") (pintype "passive"))
      (node (ref "U2") (pin "40") (pinfunction "PTC7/SDA2/SPSCK1/ADP8_40") (pintype "passive"))
      (node (ref "U4") (pin "10") (pinfunction "CLK_10") (pintype "passive"))
    )
    (net (code "42") (name "/SPI_SCK_AUX") (class "Default")
      (node (ref "P6") (pin "6") (pinfunction "6_6") (pintype "passive"))
      (node (ref "U2") (pin "54") (pinfunction "PTD7/RGPIO7/SPSCK2/ADP3_54") (pintype "passive"))
    )
    (net (code "43") (name "/SPI_~{CS2}_AUX") (class "Default")
      (node (ref "P6") (pin "3") (pinfunction "3_3") (pintype "passive"))
      (node (ref "U2") (pin "57") (pinfunction "PTE2/KBI2P2~{/SS}2/ADP0_57") (pintype "passive"))
    )
    (net (code "44") (name "/SPI_~{CS}") (class "Default")
      (node (ref "P2") (pin "3") (pinfunction "3_3") (pintype "passive"))
      (node (ref "P3") (pin "3") (pinfunction "3_3") (pintype "passive"))
      (node (ref "U2") (pin "37") (pinfunction "PTC4/IRQ~{/SS}1/ADP11_37") (pintype "passive"))
      (node (ref "U4") (pin "11") (pinfunction "CSn_11") (pintype "passive"))
    )
    (net (code "45") (name "/TXC") (class "Default")
      (node (ref "U2") (pin "20") (pinfunction "PTB3/MII_TX_CLK/MOSI1_20") (pintype "passive"))
      (node (ref "U3") (pin "33") (pinfunction "TXC_33") (pintype "output"))
    )
    (net (code "46") (name "/TXD0") (class "Default")
      (node (ref "U2") (pin "22") (pinfunction "PTB5/MII_TXD0/SPSCK1_22") (pintype "passive"))
      (node (ref "U3") (pin "35") (pinfunction "TXD0_35") (pintype "input"))
    )
    (net (code "47") (name "/TXD1") (class "Default")
      (node (ref "U2") (pin "23") (pinfunction "PTB6/MII_TXD1/TPM2CH0_23") (pintype "passive"))
      (node (ref "U3") (pin "36") (pinfunction "TXD1_36") (pintype "input"))
    )
    (net (code "48") (name "/TXD2") (class "Default")
      (node (ref "U2") (pin "24") (pinfunction "PTB7/MII_TXD2/TPM2CH1_24") (pintype "passive"))
      (node (ref "U3") (pin "38") (pinfunction "TXD2_38") (pintype "input"))
    )
    (net (code "49") (name "/TXD3") (class "Default")
      (node (ref "U2") (pin "25") (pinfunction "PTC0/MII_TXD3/TPM2CH2_25") (pintype "passive"))
      (node (ref "U3") (pin "39") (pinfunction "TXD3_39") (pintype "input"))
    )
    (net (code "50") (name "/TXEN") (class "Default")
      (node (ref "U2") (pin "21") (pinfunction "PTB4/MII_TX_EN/MISO1_21") (pintype "passive"))
      (node (ref "U3") (pin "34") (pinfunction "TXEN_34") (pintype "input"))
    )
    (net (code "51") (name "/TXM") (class "Default")
      (node (ref "C13") (pin "1") (pinfunction "1_1") (pintype "passive"))
      (node (ref "J1") (pin "2") (pinfunction "2_2") (pintype "passive"))
      (node (ref "R23") (pin "2") (pinfunction "2_2") (pintype "passive"))
    )
    (net (code "52") (name "/TXP") (class "Default")
      (node (ref "C14") (pin "1") (pinfunction "1_1") (pintype "passive"))
      (node (ref "J1") (pin "1") (pinfunction "1_1") (pintype "passive"))
      (node (ref "R21") (pin "2") (pinfunction "2_2") (pintype "passive"))
    )
    (net (code "53") (name "/VDDA") (class "Default")
      (node (ref "C8") (pin "2") (pinfunction "2_2") (pintype "passive"))
      (node (ref "C9") (pin "2") (pinfunction "2_2") (pintype "passive"))
      (node (ref "R1") (pin "2") (pinfunction "A_2") (pintype "passive"))
      (node (ref "U3") (pin "7") (pinfunction "VDDA_3.3_7") (pintype "passive"))
    )
    (net (code "54") (name "/XTAL") (class "Default")
      (node (ref "C22") (pin "2") (pinfunction "2_2") (pintype "passive"))
      (node (ref "R29") (pin "2") (pinfunction "2_2") (pintype "passive"))
      (node (ref "U2") (pin "52") (pinfunction "PTD5/RGPIO5/XTAL_52") (pintype "passive"))
      (node (ref "X1") (pin "1") (pinfunction "K_1") (pintype "passive"))
    )
    (net (code "55") (name "/~{RESET}") (class "Default")
      (node (ref "P1") (pin "4") (pinfunction "4_4") (pintype "passive"))
      (node (ref "U2") (pin "28") (pinfunction "~{RESE}T/PTC3_28") (pintype "passive"))
    )
    (net (code "56") (name "GND") (class "Default")
      (node (ref "C10") (pin "1") (pinfunction "1_1") (pintype "passive"))
      (node (ref "C15") (pin "1") (pinfunction "1_1") (pintype "passive"))
      (node (ref "C16") (pin "1") (pinfunction "1_1") (pintype "passive"))
      (node (ref "C17") (pin "1") (pinfunction "1_1") (pintype "passive"))
      (node (ref "C18") (pin "1") (pinfunction "1_1") (pintype "passive"))
      (node (ref "C19") (pin "1") (pinfunction "1_1") (pintype "passive"))
      (node (ref "C2") (pin "1") (pinfunction "1_1") (pintype "passive"))
      (node (ref "C20") (pin "1") (pinfunction "1_1") (pintype "passive"))
      (node (ref "C21") (pin "1") (pinfunction "1_1") (pintype "passive"))
      (node (ref "C22") (pin "1") (pinfunction "1_1") (pintype "passive"))
      (node (ref "C23") (pin "1") (pinfunction "1_1") (pintype "passive"))
      (node (ref "C24") (pin "1") (pinfunction "1_1") (pintype "passive"))
      (node (ref "C25") (pin "1") (pinfunction "1_1") (pintype "passive"))
      (node (ref "C27") (pin "1") (pinfunction "1_1") (pintype "passive"))
      (node (ref "C29") (pin "1") (pinfunction "1_1") (pintype "passive"))
      (node (ref "C3") (pin "1") (pinfunction "1_1") (pintype "passive"))
      (node (ref "C30") (pin "1") (pinfunction "1_1") (pintype "passive"))
      (node (ref "C31") (pin "1") (pinfunction "1_1") (pintype "passive"))
      (node (ref "C4") (pin "1") (pinfunction "1_1") (pintype "passive"))
      (node (ref "C5") (pin "1") (pinfunction "1_1") (pintype "passive"))
      (node (ref "C6") (pin "1") (pinfunction "1_1") (pintype "passive"))
      (node (ref "C7") (pin "1") (pinfunction "1_1") (pintype "passive"))
      (node (ref "C8") (pin "1") (pinfunction "1_1") (pintype "passive"))
      (node (ref "C9") (pin "1") (pinfunction "1_1") (pintype "passive"))
      (node (ref "D1") (pin "A") (pinfunction "A_A") (pintype "passive"))
      (node (ref "D2") (pin "K") (pinfunction "K_K") (pintype "passive"))
      (node (ref "D4") (pin "A") (pinfunction "A_A") (pintype "passive"))
      (node (ref "D5") (pin "A") (pinfunction "A_A") (pintype "passive"))
      (node (ref "J1") (pin "7") (pinfunction "7_7") (pintype "passive"))
      (node (ref "J1") (pin "8") (pinfunction "8_8") (pintype "passive"))
      (node (ref "P1") (pin "2") (pinfunction "2_2") (pintype "passive"))
      (node (ref "P2") (pin "1") (pinfunction "1_1") (pintype "passive"))
      (node (ref "P3") (pin "1") (pinfunction "1_1") (pintype "passive"))
      (node (ref "P6") (pin "1") (pinfunction "1_1") (pintype "passive"))
      (node (ref "P8") (pin "1") (pinfunction "1_1") (pintype "passive"))
      (node (ref "Q1") (pin "2") (pintype "passive"))
      (node (ref "Q2") (pin "2") (pintype "passive"))
      (node (ref "R12") (pin "1") (pinfunction "1_1") (pintype "passive"))
      (node (ref "R13") (pin "1") (pinfunction "1_1") (pintype "passive"))
      (node (ref "R18") (pin "1") (pinfunction "1_1") (pintype "passive"))
      (node (ref "R21") (pin "1") (pinfunction "1_1") (pintype "passive"))
      (node (ref "R23") (pin "1") (pinfunction "1_1") (pintype "passive"))
      (node (ref "R25") (pin "1") (pinfunction "1_1") (pintype "passive"))
      (node (ref "R26") (pin "1") (pinfunction "1_1") (pintype "passive"))
      (node (ref "R27") (pin "1") (pinfunction "1_1") (pintype "passive"))
      (node (ref "R6") (pin "1") (pinfunction "1_1") (pintype "passive"))
      (node (ref "U1") (pin "4") (pinfunction "RTN_4") (pintype "passive"))
      (node (ref "U2") (pin "18") (pinfunction "VSS2_18") (pintype "passive"))
      (node (ref "U2") (pin "2") (pinfunction "VSS1_2") (pintype "passive"))
      (node (ref "U2") (pin "34") (pinfunction "VSS3_34") (pintype "passive"))
      (node (ref "U2") (pin "36") (pinfunction "VSSA_36") (pintype "passive"))
      (node (ref "U2") (pin "50") (pinfunction "VSS4_50") (pintype "passive"))
      (node (ref "U3") (pin "1") (pinfunction "GND_1") (pintype "passive"))
      (node (ref "U3") (pin "13") (pinfunction "GND_13") (pintype "passive"))
      (node (ref "U3") (pin "17") (pinfunction "GND_17") (pintype "passive"))
      (node (ref "U3") (pin "2") (pinfunction "GND_2") (pintype "passive"))
      (node (ref "U3") (pin "24") (pinfunction "GND_24") (pintype "passive"))
      (node (ref "U3") (pin "3") (pinfunction "GND_3") (pintype "passive"))
      (node (ref "U3") (pin "30") (pinfunction "GND_30") (pintype "passive"))
      (node (ref "U3") (pin "37") (pinfunction "GND_37") (pintype "passive"))
      (node (ref "U4") (pin "7") (pinfunction "VSS_7") (pintype "passive"))
      (node (ref "U4") (pin "8") (pinfunction "Prog_DI_8") (pintype "passive"))
      (node (ref "U5") (pin "5") (pinfunction "V-_5") (pintype "power_in"))
      (node (ref "U7") (pin "0") (pinfunction "PADDLE_0") (pintype "passive"))
      (node (ref "U7") (pin "2") (pinfunction "GND_2") (pintype "passive"))
    )
    (net (code "57") (name "Net-(C27-Pad2)") (class "Default")
      (node (ref "C27") (pin "2") (pinfunction "2_2") (pintype "passive"))
      (node (ref "R22") (pin "1") (pinfunction "1_1") (pintype "passive"))
      (node (ref "R24") (pin "2") (pinfunction "2_2") (pintype "passive"))
    )
    (net (code "58") (name "Net-(D2-PadA)") (class "Default")
      (node (ref "D2") (pin "A") (pinfunction "A_A") (pintype "passive"))
      (node (ref "R30") (pin "1") (pinfunction "1_1") (pintype "passive"))
    )
    (net (code "59") (name "Net-(D3-PadA)") (class "Default")
      (node (ref "D3") (pin "A") (pinfunction "A_A") (pintype "passive"))
      (node (ref "R31") (pin "1") (pinfunction "1_1") (pintype "passive"))
    )
    (net (code "60") (name "Net-(Q1-Pad3)") (class "Default")
      (node (ref "Q1") (pin "3") (pintype "passive"))
      (node (ref "R15") (pin "1") (pinfunction "1_1") (pintype "passive"))
    )
    (net (code "61") (name "Net-(Q2-Pad3)") (class "Default")
      (node (ref "Q2") (pin "3") (pintype "passive"))
      (node (ref "R16") (pin "1") (pinfunction "1_1") (pintype "passive"))
    )
    (net (code "62") (name "Net-(Q3-B)") (class "Default")
      (node (ref "Q3") (pin "3") (pinfunction "B_3") (pintype "passive"))
      (node (ref "R15") (pin "2") (pinfunction "2_2") (pintype "passive"))
    )
    (net (code "63") (name "Net-(Q4-B)") (class "Default")
      (node (ref "Q4") (pin "3") (pinfunction "B_3") (pintype "passive"))
      (node (ref "R16") (pin "2") (pinfunction "2_2") (pintype "passive"))
    )
    (net (code "64") (name "Net-(R8-A)") (class "Default")
      (node (ref "C2") (pin "2") (pinfunction "2_2") (pintype "passive"))
      (node (ref "R11") (pin "2") (pinfunction "2_2") (pintype "passive"))
      (node (ref "R8") (pin "2") (pinfunction "A_2") (pintype "passive"))
      (node (ref "U1") (pin "8") (pinfunction "Vin_8") (pintype "passive"))
    )
    (net (code "65") (name "Net-(U1-BST)") (class "Default")
      (node (ref "C1") (pin "1") (pinfunction "1_1") (pintype "passive"))
      (node (ref "U1") (pin "2") (pinfunction "BST_2") (pintype "passive"))
    )
    (net (code "66") (name "Net-(U1-FB)") (class "Default")
      (node (ref "R12") (pin "2") (pinfunction "2_2") (pintype "passive"))
      (node (ref "R9") (pin "1") (pinfunction "1_1") (pintype "passive"))
      (node (ref "U1") (pin "5") (pinfunction "FB_5") (pintype "passive"))
    )
    (net (code "67") (name "Net-(U1-Rcl)") (class "Default")
      (node (ref "R13") (pin "2") (pinfunction "2_2") (pintype "passive"))
      (node (ref "U1") (pin "3") (pinfunction "Rcl_3") (pintype "passive"))
    )
    (net (code "68") (name "Net-(U1-Ron)") (class "Default")
      (node (ref "R11") (pin "1") (pinfunction "1_1") (pintype "passive"))
      (node (ref "U1") (pin "6") (pinfunction "Ron_6") (pintype "passive"))
    )
    (net (code "69") (name "Net-(U1-SW)") (class "Default")
      (node (ref "C1") (pin "2") (pinfunction "2_2") (pintype "passive"))
      (node (ref "D1") (pin "K") (pinfunction "K_K") (pintype "passive"))
      (node (ref "L1") (pin "1") (pinfunction "1_1") (pintype "passive"))
      (node (ref "U1") (pin "1") (pinfunction "SW_1") (pintype "passive"))
    )
    (net (code "70") (name "Net-(U1-Vcc)") (class "Default")
      (node (ref "C23") (pin "2") (pinfunction "2_2") (pintype "passive"))
      (node (ref "U1") (pin "7") (pinfunction "Vcc_7") (pintype "passive"))
    )
    (net (code "71") (name "Net-(U3-REXT)") (class "Default")
      (node (ref "R6") (pin "2") (pinfunction "2_2") (pintype "passive"))
      (node (ref "U3") (pin "16") (pinfunction "REXT_16") (pintype "passive"))
    )
    (net (code "72") (name "Net-(U3-RXM)") (class "Default")
      (node (ref "C11") (pin "2") (pinfunction "2_2") (pintype "passive"))
      (node (ref "R5") (pin "1") (pinfunction "1_1") (pintype "passive"))
      (node (ref "U3") (pin "9") (pinfunction "RXM_9") (pintype "passive"))
    )
    (net (code "73") (name "Net-(U3-RXP)") (class "Default")
      (node (ref "C12") (pin "2") (pinfunction "2_2") (pintype "passive"))
      (node (ref "R4") (pin "1") (pinfunction "1_1") (pintype "passive"))
      (node (ref "U3") (pin "10") (pinfunction "RXP_10") (pintype "passive"))
    )
    (net (code "74") (name "Net-(U3-TXM)") (class "Default")
      (node (ref "C13") (pin "2") (pinfunction "2_2") (pintype "passive"))
      (node (ref "R3") (pin "1") (pinfunction "1_1") (pintype "passive"))
      (node (ref "U3") (pin "11") (pinfunction "TXM_11") (pintype "passive"))
    )
    (net (code "75") (name "Net-(U3-TXP)") (class "Default")
      (node (ref "C14") (pin "2") (pinfunction "2_2") (pintype "passive"))
      (node (ref "R2") (pin "1") (pinfunction "1_1") (pintype "passive"))
      (node (ref "U3") (pin "12") (pinfunction "TXP_12") (pintype "passive"))
    )
    (net (code "76") (name "Net-(U5-IN+_A)") (class "Default")
      (node (ref "R20") (pin "2") (pinfunction "2_2") (pintype "passive"))
      (node (ref "R24") (pin "1") (pinfunction "1_1") (pintype "passive"))
      (node (ref "R26") (pin "2") (pinfunction "2_2") (pintype "passive"))
      (node (ref "U5") (pin "3") (pinfunction "IN+_A_3") (pintype "input"))
    )
    (net (code "77") (name "Net-(U5-IN-_A)") (class "Default")
      (node (ref "R10") (pin "1") (pinfunction "1_1") (pintype "passive"))
      (node (ref "R28") (pin "1") (pinfunction "1_1") (pintype "passive"))
      (node (ref "U5") (pin "4") (pinfunction "IN-_A_4") (pintype "input"))
    )
    (net (code "78") (name "VALVE_PWR") (class "Default")
      (node (ref "C29") (pin "2") (pinfunction "2_2") (pintype "passive"))
      (node (ref "C30") (pin "2") (pinfunction "2_2") (pintype "passive"))
      (node (ref "P7") (pin "1") (pinfunction "1_1") (pintype "passive"))
      (node (ref "P8") (pin "2") (pinfunction "2_2") (pintype "passive"))
      (node (ref "Q3") (pin "1") (pinfunction "E_1") (pintype "passive"))
      (node (ref "Q4") (pin "1") (pinfunction "E_1") (pintype "passive"))
    )
    (net (code "79") (name "VIN") (class "Default")
      (node (ref "J1") (pin "4") (pinfunction "4_4") (pintype "passive"))
      (node (ref "J1") (pin "5") (pinfunction "5_5") (pintype "passive"))
      (node (ref "P7") (pin "2") (pinfunction "2_2") (pintype "passive"))
      (node (ref "R8") (pin "1") (pinfunction "K_1") (pintype "passive"))
    )
    (net (code "80") (name "unconnected-(P1-Pad3)") (class "Default")
      (node (ref "P1") (pin "3") (pinfunction "3_3") (pintype "passive+no_connect"))
    )
    (net (code "81") (name "unconnected-(P1-Pad5)") (class "Default")
      (node (ref "P1") (pin "5") (pinfunction "5_5") (pintype "passive+no_connect"))
    )
    (net (code "82") (name "unconnected-(U2-PTB2{slash}MII_TX_ER~{{slash}SS}1-Pad19)") (class "Default")
      (node (ref "U2") (pin "19") (pinfunction "PTB2/MII_TX_ER~{/SS}1_19") (pintype "passive"))
    )
    (net (code "83") (name "unconnected-(U2-PTC5{slash}MOSI1{slash}ADP10-Pad38)") (class "Default")
      (node (ref "U2") (pin "38") (pinfunction "PTC5/MOSI1/ADP10_38") (pintype "passive"))
    )
    (net (code "84") (name "unconnected-(U2-PTE6{slash}KBI2P6{slash}FB_D0{slash}TXD3-Pad61)") (class "Default")
      (node (ref "U2") (pin "61") (pinfunction "PTE6/KBI2P6/FB_D0/TXD3_61") (pintype "passive+no_connect"))
    )
    (net (code "85") (name "unconnected-(U2-PTE7{slash}KBI2P7~{{slash}FB_CS}0{slash}RXD3-Pad62)") (class "Default")
      (node (ref "U2") (pin "62") (pinfunction "PTE7/KBI2P7~{/FB_CS}0/RXD3_62") (pintype "passive+no_connect"))
    )
    (net (code "86") (name "unconnected-(U2-PTF2{slash}RGPIO10{slash}FB_A17{slash}FB_AD17-Pad15)") (class "Default")
      (node (ref "U2") (pin "15") (pinfunction "PTF2/RGPIO10/FB_A17/FB_AD17_15") (pintype "passive+no_connect"))
    )
    (net (code "87") (name "unconnected-(U2-PTF3{slash}RGPIO11{slash}FB_A16{slash}FB_AD16-Pad16)") (class "Default")
      (node (ref "U2") (pin "16") (pinfunction "PTF3/RGPIO11/FB_A16/FB_AD16_16") (pintype "passive+no_connect"))
    )
    (net (code "88") (name "unconnected-(U2-PTF6{slash}RGPIO14{slash}FB_A14{slash}FB_AD14{slash}TPM2CH1-Pad31)") (class "Default")
      (node (ref "U2") (pin "31") (pinfunction "PTF6/RGPIO14/FB_A14/FB_AD14/TPM2CH1_31") (pintype "passive+no_connect"))
    )
    (net (code "89") (name "unconnected-(U2-PTF7{slash}RGPIO15{slash}FB_A13{slash}FB_AD13{slash}TPM2CH2-Pad32)") (class "Default")
      (node (ref "U2") (pin "32") (pinfunction "PTF7/RGPIO15/FB_A13/FB_AD13/TPM2CH2_32") (pintype "passive+no_connect"))
    )
    (net (code "90") (name "unconnected-(U2-PTG2{slash}KBI1P2{slash}FB_A6{slash}FB_AD6{slash}SCL1-Pad47)") (class "Default")
      (node (ref "U2") (pin "47") (pinfunction "PTG2/KBI1P2/FB_A6/FB_AD6/SCL1_47") (pintype "passive+no_connect"))
    )
    (net (code "91") (name "unconnected-(U2-PTG3{slash}KBI1P3{slash}FB_A5{slash}FB_AD5{slash}SDA1-Pad48)") (class "Default")
      (node (ref "U2") (pin "48") (pinfunction "PTG3/KBI1P3/FB_A5/FB_AD5/SDA1_48") (pintype "passive+no_connect"))
    )
    (net (code "92") (name "unconnected-(U2-PTJ0{slash}FB_ALE~{{slash}FB_CS}1-Pad63)") (class "Default")
      (node (ref "U2") (pin "63") (pinfunction "PTJ0/FB_ALE~{/FB_CS}1_63") (pintype "passive+no_connect"))
    )
    (net (code "93") (name "unconnected-(U2-PTJ1{slash}FB_A4{slash}FB_AD4-Pad64)") (class "Default")
      (node (ref "U2") (pin "64") (pinfunction "PTJ1/FB_A4/FB_AD4_64") (pintype "passive+no_connect"))
    )
    (net (code "94") (name "unconnected-(U3-INTRP{slash}NAND_TREE#-Pad32)") (class "Default")
      (node (ref "U3") (pin "32") (pinfunction "INTRP/NAND_TREE#_32") (pintype "passive+no_connect"))
    )
    (net (code "95") (name "unconnected-(U3-LED0{slash}NWAYEN-Pad42)") (class "Default")
      (node (ref "U3") (pin "42") (pinfunction "LED0/NWAYEN_42") (pintype "passive+no_connect"))
    )
    (net (code "96") (name "unconnected-(U3-LED1{slash}SPEED-Pad43)") (class "Default")
      (node (ref "U3") (pin "43") (pinfunction "LED1/SPEED_43") (pintype "passive+no_connect"))
    )
    (net (code "97") (name "unconnected-(U3-SPEED-Pad43)") (class "Default")
      (node (ref "U3") (pin "43") (pinfunction "SPEED_43") (pintype "passive"))
    )
    (net (code "98") (name "unconnected-(U3-XO-Pad14)") (class "Default")
      (node (ref "U3") (pin "14") (pinfunction "XO_14") (pintype "passive+no_connect"))
    )
    (net (code "99") (name "unconnected-(U4-MagDECn-Pad2)") (class "Default")
      (node (ref "U4") (pin "2") (pinfunction "MagDECn_2") (pintype "passive+no_connect"))
    )
    (net (code "100") (name "unconnected-(U4-MagINCn-Pad1)") (class "Default")
      (node (ref "U4") (pin "1") (pinfunction "MagINCn_1") (pintype "passive+no_connect"))
    )
    (net (code "101") (name "unconnected-(U4-Mode-Pad6)") (class "Default")
      (node (ref "U4") (pin "6") (pinfunction "Mode_6") (pintype "passive+no_connect"))
    )
    (net (code "102") (name "unconnected-(U4-PWM-Pad12)") (class "Default")
      (node (ref "U4") (pin "12") (pinfunction "PWM_12") (pintype "passive+no_connect"))
    )
  )
)
